# SCH_NFC-Business-Card_2024-08-17.net
KiCad netlist of a schematic drawn in EasyEDA
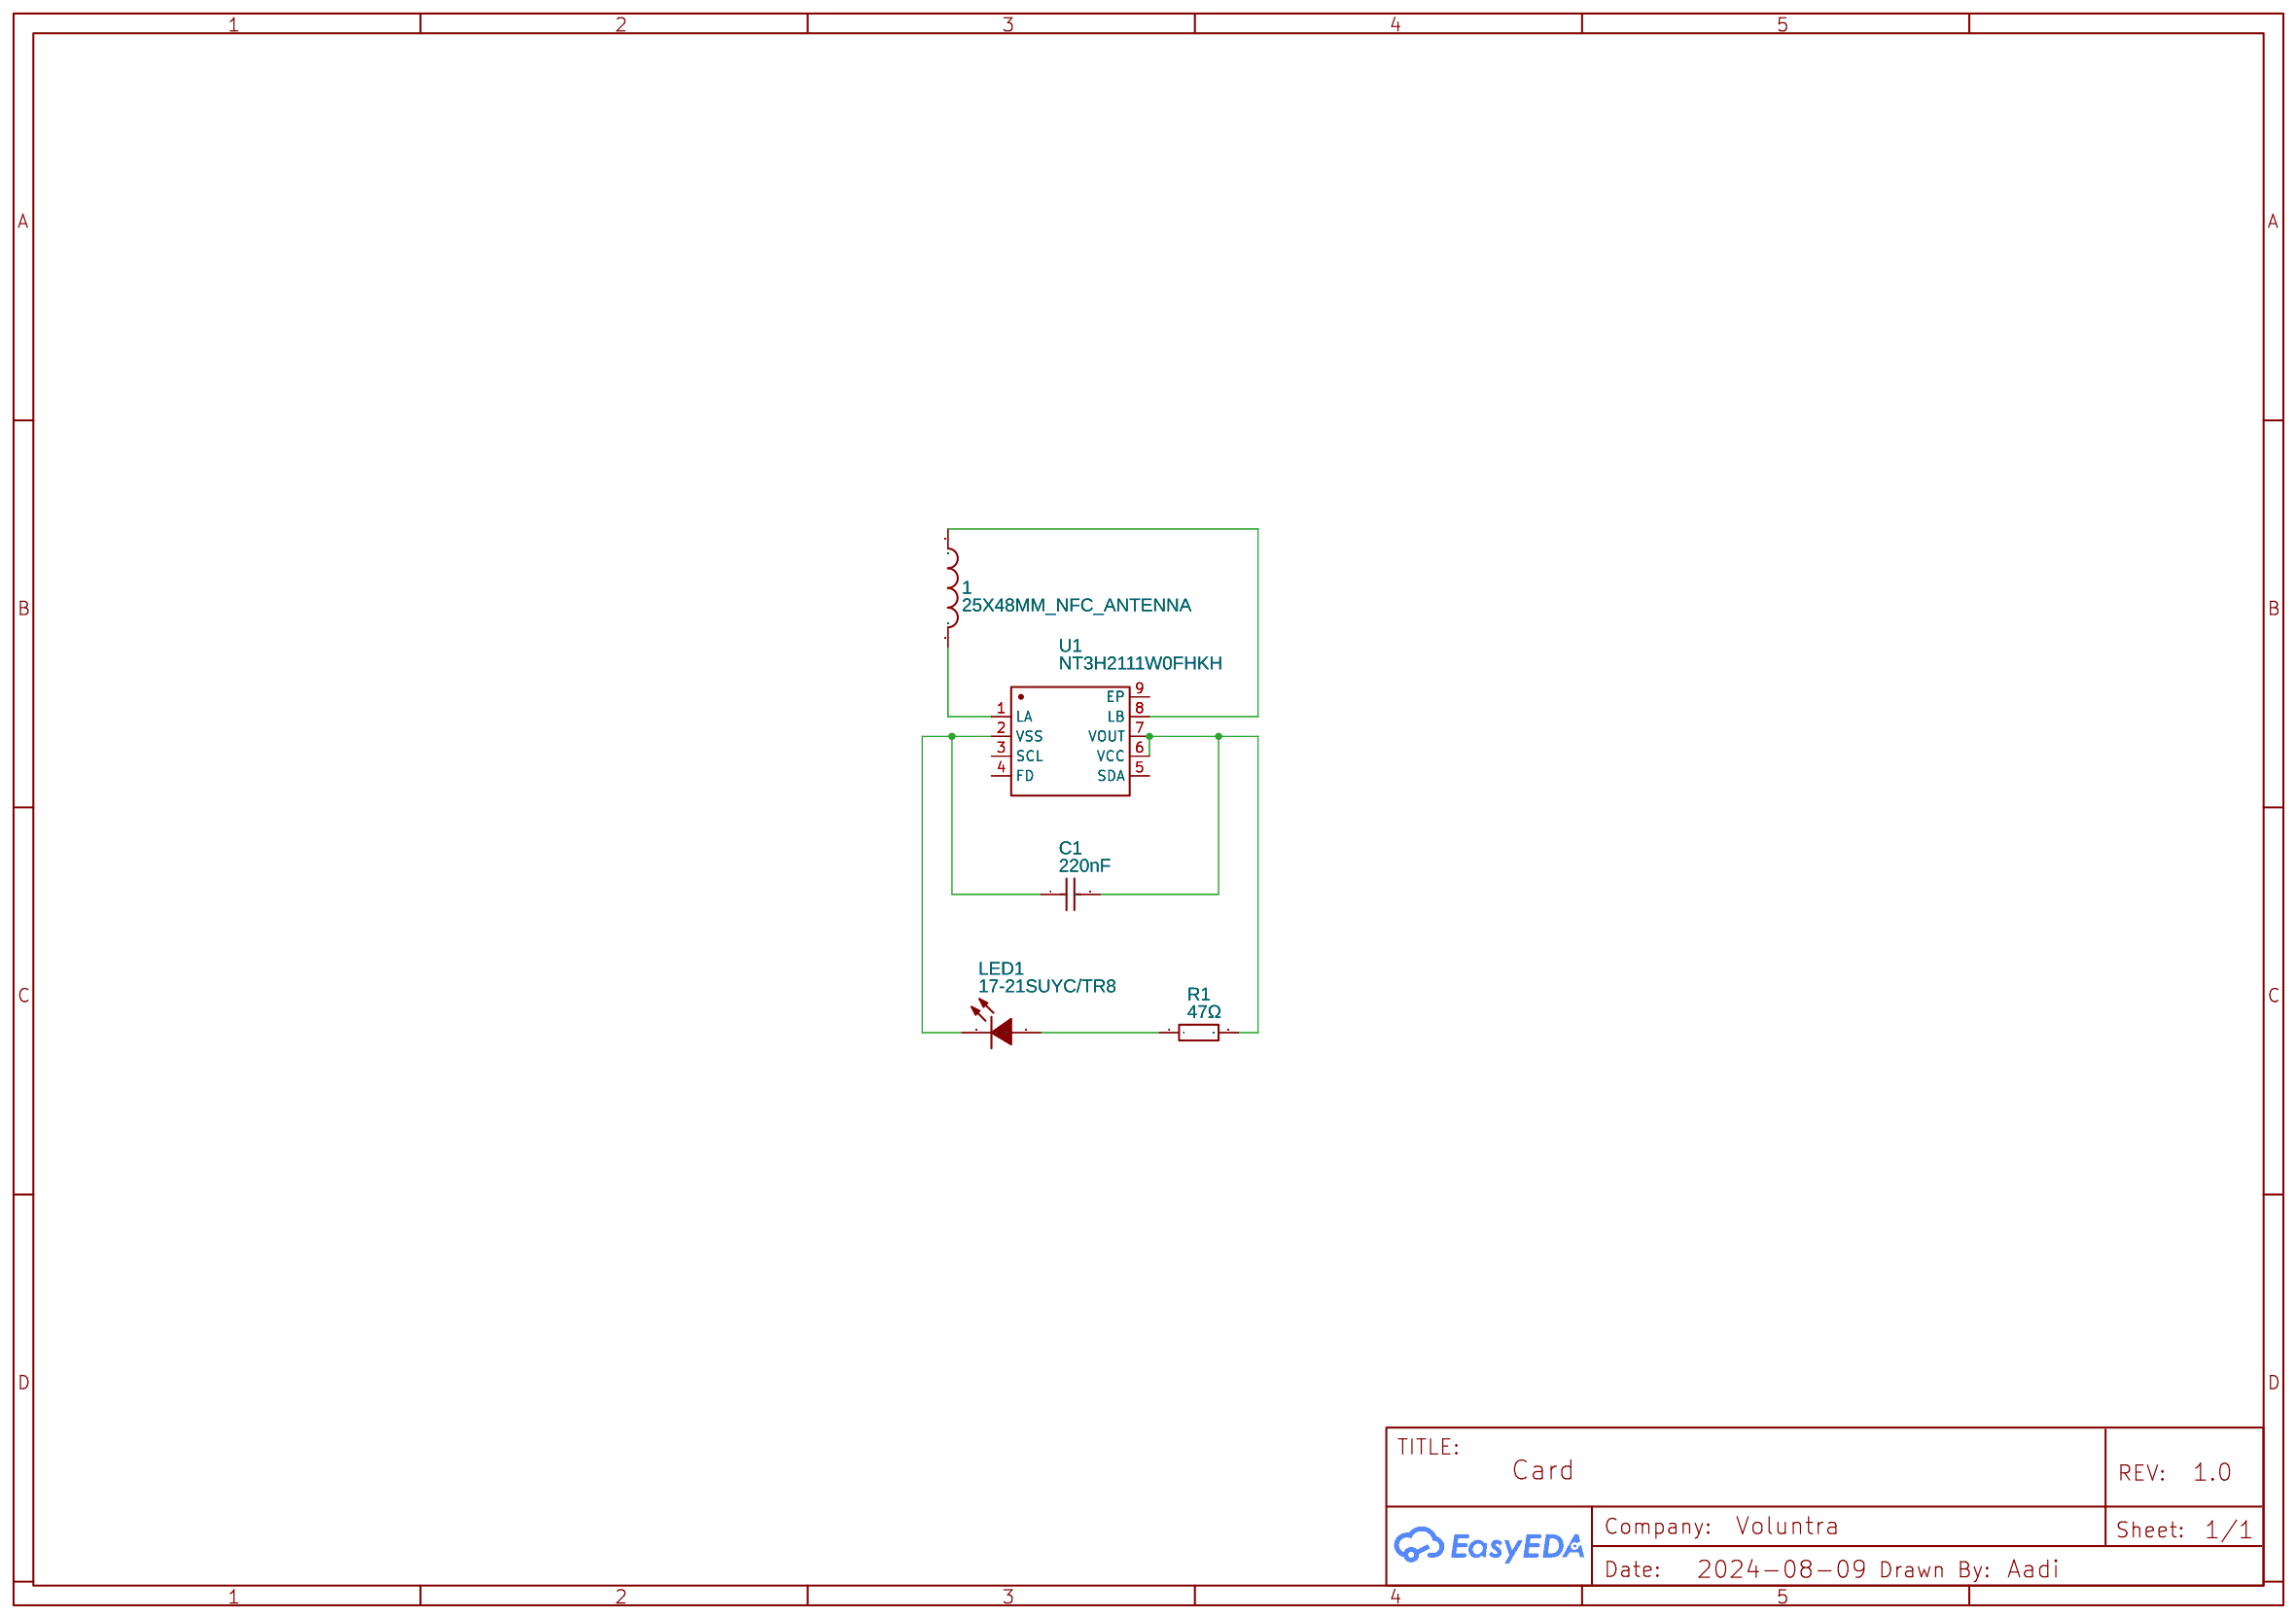
[diagram p0: schematic sheet]

(export (version "E")
  (design (tool "Eeschema 10.0.6"))
  (components
    (comp (ref "1") (value "25X48MM_NFC_ANTENNA") (libsource (lib "") (part "25X48MM_NFC_ANTENNA")))
    (comp (ref "C1")
      (value "220nF")
      (fields
        (field (name "Manufacturer Part") "CL10B224KA8NNNC")
        (field (name "Manufacturer") "SAMSUNG(三星)")
      )
      (libsource (lib "") (part "CL10B224KA8NNNC"))
    )
    (comp (ref "LED1")
      (value "17-21SUYC/TR8")
      (fields (field (name "Manufacturer Part") "KT-0805黄灯") (field (name "Manufacturer") "KENTO"))
      (libsource (lib "") (part "17-21SUYC/TR8"))
    )
    (comp (ref "R1")
      (value "47Ω")
      (fields
        (field (name "Manufacturer Part") "0603WAF470JT5E")
        (field (name "Manufacturer") "UNI-ROYAL(厚声)")
      )
      (libsource (lib "") (part "0603WAF470JT5E"))
    )
    (comp (ref "U1")
      (value "NT3H2111W0FHKH")
      (fields (field (name "Manufacturer") "NXP(恩智浦)"))
      (libsource (lib "") (part "NT3H2111W0FHKH"))
    )
  )
  (nets
    (net (code "1") (name "Net-(LED1-+)") (class "Default")
      (node (ref "LED1") (pin "1") (pinfunction "+_1") (pintype "unspecified"))
      (node (ref "R1") (pin "1") (pinfunction "1_1") (pintype "input"))
    )
    (net (code "2") (name "Net-(LED1--)") (class "Default")
      (node (ref "C1") (pin "1") (pinfunction "1_1") (pintype "input"))
      (node (ref "LED1") (pin "2") (pinfunction "-_2") (pintype "unspecified"))
      (node (ref "U1") (pin "2") (pinfunction "VSS_2") (pintype "unspecified"))
    )
    (net (code "3") (name "Net-(U1-LA)") (class "Default")
      (node (ref "1") (pin "P$2") (pinfunction "P$2_P$2") (pintype "bidirectional"))
      (node (ref "U1") (pin "1") (pinfunction "LA_1") (pintype "unspecified"))
    )
    (net (code "4") (name "Net-(U1-LB)") (class "Default")
      (node (ref "1") (pin "P$1") (pinfunction "P$1_P$1") (pintype "bidirectional"))
      (node (ref "U1") (pin "8") (pinfunction "LB_8") (pintype "unspecified"))
    )
    (net (code "5") (name "Net-(U1-VCC)") (class "Default")
      (node (ref "C1") (pin "2") (pinfunction "2_2") (pintype "input"))
      (node (ref "R1") (pin "2") (pinfunction "2_2") (pintype "input"))
      (node (ref "U1") (pin "6") (pinfunction "VCC_6") (pintype "unspecified"))
      (node (ref "U1") (pin "7") (pinfunction "VOUT_7") (pintype "unspecified"))
    )
    (net (code "6") (name "unconnected-(U1-EP-Pad9)") (class "Default")
      (node (ref "U1") (pin "9") (pinfunction "EP_9") (pintype "unspecified"))
    )
    (net (code "7") (name "unconnected-(U1-FD-Pad4)") (class "Default")
      (node (ref "U1") (pin "4") (pinfunction "FD_4") (pintype "unspecified"))
    )
    (net (code "8") (name "unconnected-(U1-SCL-Pad3)") (class "Default")
      (node (ref "U1") (pin "3") (pinfunction "SCL_3") (pintype "unspecified"))
    )
    (net (code "9") (name "unconnected-(U1-SDA-Pad5)") (class "Default")
      (node (ref "U1") (pin "5") (pinfunction "SDA_5") (pintype "unspecified"))
    )
  )
)
